# Un_Arduino_old.net
KiCad netlist of a schematic drawn in EAGLE
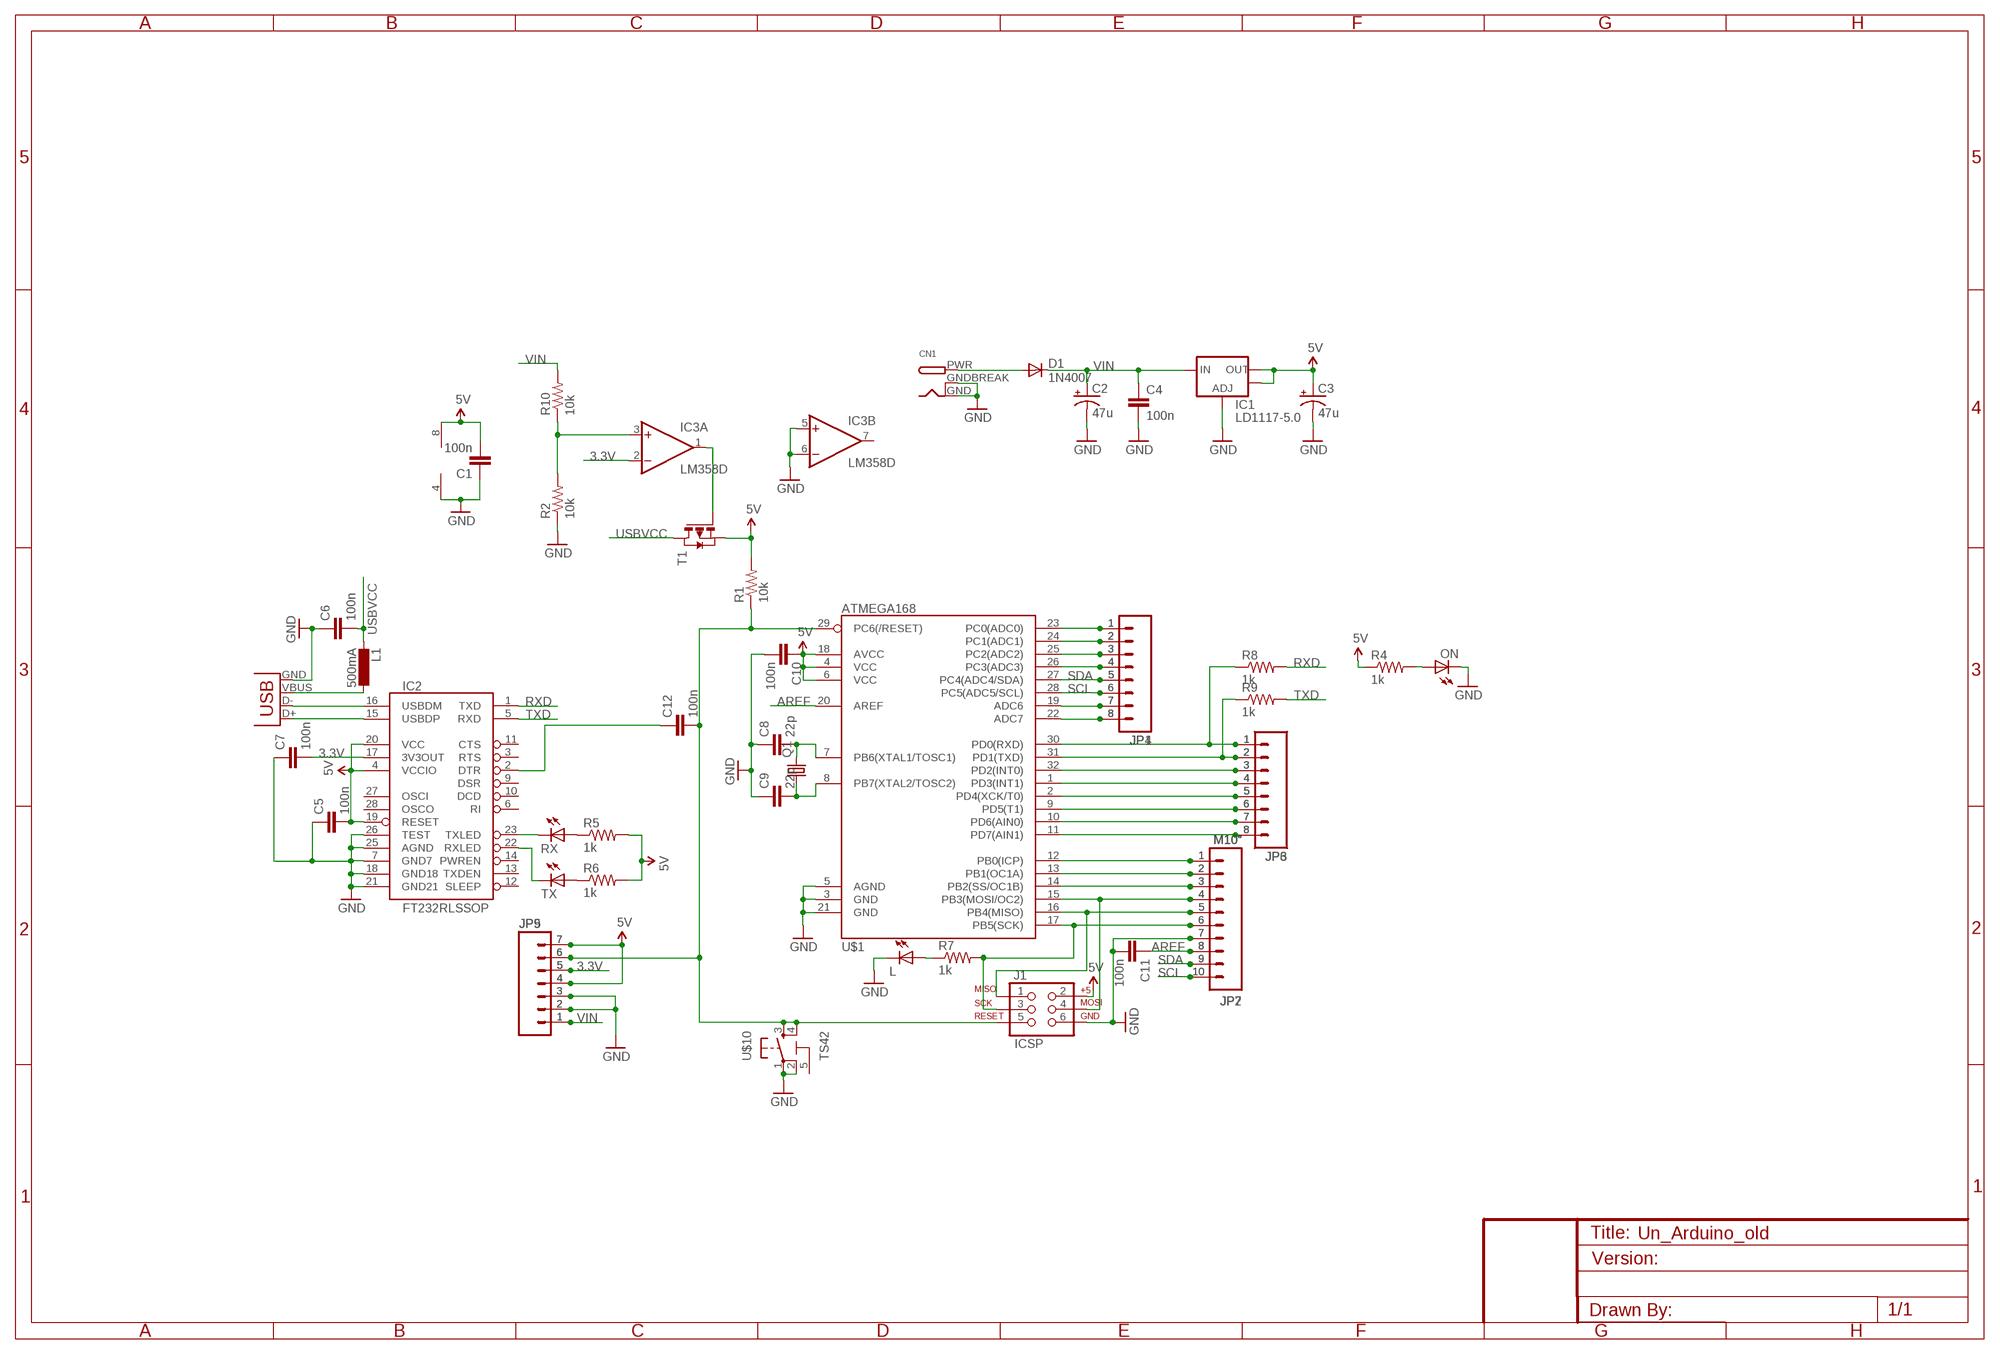
[diagram p0: schematic, sheet 1]

(export (version "E")
  (design (tool "Eeschema 10.0.6"))
  (components
    (comp (ref "C1")
      (value "100n")
      (footprint "eagle-import:0603-CAP")
      (libsource (lib "eagle-import") (part "CAP0603-CAP"))
    )
    (comp (ref "C2")
      (value "47u")
      (footprint "eagle-import:PANASONIC_D")
      (libsource (lib "eagle-import") (part "CAP_POLD"))
    )
    (comp (ref "C3")
      (value "47u")
      (footprint "eagle-import:PANASONIC_D")
      (libsource (lib "eagle-import") (part "CAP_POLD"))
    )
    (comp (ref "C4")
      (value "100n")
      (footprint "eagle-import:0603-CAP")
      (libsource (lib "eagle-import") (part "CAP0603-CAP"))
    )
    (comp (ref "C5")
      (value "100n")
      (footprint "eagle-import:0603-CAP")
      (libsource (lib "eagle-import") (part "CAP0603-CAP"))
    )
    (comp (ref "C6")
      (value "100n")
      (footprint "eagle-import:0603-CAP")
      (libsource (lib "eagle-import") (part "CAP0603-CAP"))
    )
    (comp (ref "C7")
      (value "100n")
      (footprint "eagle-import:0603-CAP")
      (libsource (lib "eagle-import") (part "CAP0603-CAP"))
    )
    (comp (ref "C8")
      (value "22p")
      (footprint "eagle-import:0805")
      (libsource (lib "eagle-import") (part "CAP0805"))
    )
    (comp (ref "C9")
      (value "22p")
      (footprint "eagle-import:0805")
      (libsource (lib "eagle-import") (part "CAP0805"))
    )
    (comp (ref "C10")
      (value "100n")
      (footprint "eagle-import:0603-CAP")
      (libsource (lib "eagle-import") (part "CAP0603-CAP"))
    )
    (comp (ref "C11")
      (value "100n")
      (footprint "eagle-import:0603-CAP")
      (libsource (lib "eagle-import") (part "CAP0603-CAP"))
    )
    (comp (ref "C12")
      (value "100n")
      (footprint "eagle-import:0603-CAP")
      (libsource (lib "eagle-import") (part "CAP0603-CAP"))
    )
    (comp (ref "CN1")
      (value "DCBARRELPTH")
      (footprint "eagle-import:DCJACK_2MM_PTH")
      (libsource (lib "eagle-import") (part "DCBARRELPTH"))
    )
    (comp (ref "D1")
      (value "1N4007")
      (footprint "eagle-import:SMB")
      (libsource (lib "eagle-import") (part "DIODE-SMB"))
    )
    (comp (ref "IC1")
      (value "LD1117-5.0")
      (footprint "eagle-import:SOT223")
      (libsource (lib "eagle-import") (part "V_REG_LM1117SOT223"))
    )
    (comp (ref "IC2")
      (value "FT232RLSSOP")
      (footprint "eagle-import:SSOP28DB")
      (libsource (lib "eagle-import") (part "FT232RLSSOP"))
    )
    (comp (ref "IC3")
      (value "LM358D")
      (footprint "eagle-import:SO08")
      (libsource (lib "eagle-import") (part "LM358D"))
    )
    (comp (ref "J1")
      (value "ICSP")
      (footprint "eagle-import:2X3")
      (libsource (lib "eagle-import") (part "AVR_SPI_PRG_6PTH"))
    )
    (comp (ref "JP1")
      (value "M081X08")
      (footprint "eagle-import:1X08")
      (libsource (lib "eagle-import") (part "M081X08"))
    )
    (comp (ref "JP2")
      (value "M10\"")
      (footprint "eagle-import:1X10")
      (libsource (lib "eagle-import") (part "M10{dblquote}"))
    )
    (comp (ref "JP3")
      (value "M08")
      (footprint "eagle-import:1X08")
      (libsource (lib "eagle-import") (part "M08"))
    )
    (comp (ref "JP4")
      (value "M081X08")
      (footprint "eagle-import:1X08")
      (libsource (lib "eagle-import") (part "M081X08"))
    )
    (comp (ref "JP5")
      (value "M07")
      (footprint "eagle-import:1X07")
      (libsource (lib "eagle-import") (part "M07"))
    )
    (comp (ref "JP6")
      (value "M08")
      (footprint "eagle-import:1X08")
      (libsource (lib "eagle-import") (part "M08"))
    )
    (comp (ref "JP7")
      (value "M10\"")
      (footprint "eagle-import:1X10")
      (libsource (lib "eagle-import") (part "M10{dblquote}"))
    )
    (comp (ref "JP9")
      (value "M07")
      (footprint "eagle-import:1X07")
      (libsource (lib "eagle-import") (part "M07"))
    )
    (comp (ref "L")
      (value "LED0805")
      (footprint "eagle-import:LED-0805")
      (libsource (lib "eagle-import") (part "LED0805"))
    )
    (comp (ref "L1")
      (value "500mA")
      (footprint "eagle-import:L1812")
      (libsource (lib "eagle-import") (part "L-EUL1812"))
    )
    (comp (ref "ON")
      (value "LED0805")
      (footprint "eagle-import:LED-0805")
      (libsource (lib "eagle-import") (part "LED0805"))
    )
    (comp (ref "Q1")
      (value "CRYSTALHC49US")
      (footprint "eagle-import:HC49US")
      (libsource (lib "eagle-import") (part "CRYSTALHC49US"))
    )
    (comp (ref "R1")
      (value "10k")
      (footprint "eagle-import:0805")
      (libsource (lib "eagle-import") (part "RESISTOR0805-RES"))
    )
    (comp (ref "R2")
      (value "10k")
      (footprint "eagle-import:0805")
      (libsource (lib "eagle-import") (part "RESISTOR0805-RES"))
    )
    (comp (ref "R4")
      (value "1k")
      (footprint "eagle-import:0805")
      (libsource (lib "eagle-import") (part "RESISTOR0805-RES"))
    )
    (comp (ref "R5")
      (value "1k")
      (footprint "eagle-import:0805")
      (libsource (lib "eagle-import") (part "RESISTOR0805-RES"))
    )
    (comp (ref "R6")
      (value "1k")
      (footprint "eagle-import:0805")
      (libsource (lib "eagle-import") (part "RESISTOR0805-RES"))
    )
    (comp (ref "R7")
      (value "1k")
      (footprint "eagle-import:0805")
      (libsource (lib "eagle-import") (part "RESISTOR0805-RES"))
    )
    (comp (ref "R8")
      (value "1k")
      (footprint "eagle-import:0805")
      (libsource (lib "eagle-import") (part "RESISTOR0805-RES"))
    )
    (comp (ref "R9")
      (value "1k")
      (footprint "eagle-import:0805")
      (libsource (lib "eagle-import") (part "RESISTOR0805-RES"))
    )
    (comp (ref "R10")
      (value "10k")
      (footprint "eagle-import:0805")
      (libsource (lib "eagle-import") (part "RESISTOR0805-RES"))
    )
    (comp (ref "RX")
      (value "LED0805")
      (footprint "eagle-import:LED-0805")
      (libsource (lib "eagle-import") (part "LED0805"))
    )
    (comp (ref "T1")
      (value "PMOSSOT23")
      (footprint "eagle-import:SOT-23")
      (libsource (lib "eagle-import") (part "PMOSSOT23"))
    )
    (comp (ref "TX")
      (value "LED0805")
      (footprint "eagle-import:LED-0805")
      (libsource (lib "eagle-import") (part "LED0805"))
    )
    (comp (ref "U$1")
      (value "ATMEGA168")
      (footprint "eagle-import:TQFP32-08")
      (libsource (lib "eagle-import") (part "ATMEGA168"))
    )
    (comp (ref "U$10")
      (value "TS42")
      (footprint "eagle-import:TS42")
      (libsource (lib "eagle-import") (part "TS42"))
    )
    (comp (ref "X1")
      (value "USBPTH")
      (footprint "eagle-import:USB-B-PTH")
      (libsource (lib "eagle-import") (part "USBPTH"))
    )
  )
  (nets
    (net (code "1") (name "/3.3V") (class "Default")
      (node (ref "C7") (pin "2") (pinfunction "2_2") (pintype "passive"))
      (node (ref "IC2") (pin "17") (pinfunction "3V3OUT_17") (pintype "output"))
      (node (ref "IC3") (pin "2") (pinfunction "-IN_2") (pintype "input"))
      (node (ref "JP5") (pin "5") (pinfunction "5_5") (pintype "passive"))
      (node (ref "JP9") (pin "5") (pinfunction "5_5") (pintype "passive"))
    )
    (net (code "2") (name "/AREF") (class "Default")
      (node (ref "C11") (pin "1") (pinfunction "1_1") (pintype "passive"))
      (node (ref "JP2") (pin "8") (pinfunction "8_8") (pintype "passive"))
      (node (ref "JP7") (pin "8") (pinfunction "8_8") (pintype "passive"))
      (node (ref "U$1") (pin "20") (pinfunction "AREF_20") (pintype "bidirectional"))
    )
    (net (code "3") (name "/RXD") (class "Default")
      (node (ref "IC2") (pin "1") (pinfunction "TXD_1") (pintype "output"))
      (node (ref "R8") (pin "2") (pinfunction "2_2") (pintype "passive"))
    )
    (net (code "4") (name "/SCL") (class "Default")
      (node (ref "JP1") (pin "6") (pinfunction "6_6") (pintype "passive"))
      (node (ref "JP2") (pin "10") (pinfunction "10_10") (pintype "passive"))
      (node (ref "JP4") (pin "6") (pinfunction "6_6") (pintype "passive"))
      (node (ref "JP7") (pin "10") (pinfunction "10_10") (pintype "passive"))
      (node (ref "U$1") (pin "28") (pinfunction "PC5(ADC5/SCL)_28") (pintype "bidirectional"))
    )
    (net (code "5") (name "/SDA") (class "Default")
      (node (ref "JP1") (pin "5") (pinfunction "5_5") (pintype "passive"))
      (node (ref "JP2") (pin "9") (pinfunction "9_9") (pintype "passive"))
      (node (ref "JP4") (pin "5") (pinfunction "5_5") (pintype "passive"))
      (node (ref "JP7") (pin "9") (pinfunction "9_9") (pintype "passive"))
      (node (ref "U$1") (pin "27") (pinfunction "PC4(ADC4/SDA)_27") (pintype "bidirectional"))
    )
    (net (code "6") (name "/TXD") (class "Default")
      (node (ref "IC2") (pin "5") (pinfunction "RXD_5") (pintype "input"))
      (node (ref "R9") (pin "2") (pinfunction "2_2") (pintype "passive"))
    )
    (net (code "7") (name "/USBVCC") (class "Default")
      (node (ref "C6") (pin "2") (pinfunction "2_2") (pintype "passive"))
      (node (ref "L1") (pin "2") (pinfunction "2_2") (pintype "passive"))
      (node (ref "T1") (pin "1") (pinfunction "D_1") (pintype "passive"))
    )
    (net (code "8") (name "/VIN") (class "Default")
      (node (ref "C2") (pin "+") (pinfunction "+_+") (pintype "passive"))
      (node (ref "C4") (pin "1") (pinfunction "1_1") (pintype "passive"))
      (node (ref "D1") (pin "C") (pinfunction "C_C") (pintype "passive"))
      (node (ref "IC1") (pin "3") (pinfunction "IN_3") (pintype "input"))
      (node (ref "JP5") (pin "1") (pinfunction "1_1") (pintype "passive"))
      (node (ref "JP9") (pin "1") (pinfunction "1_1") (pintype "passive"))
      (node (ref "R10") (pin "2") (pinfunction "2_2") (pintype "passive"))
    )
    (net (code "9") (name "5V") (class "Default")
      (node (ref "C1") (pin "2") (pinfunction "2_2") (pintype "passive"))
      (node (ref "C10") (pin "1") (pinfunction "1_1") (pintype "passive"))
      (node (ref "C3") (pin "+") (pinfunction "+_+") (pintype "passive"))
      (node (ref "C5") (pin "2") (pinfunction "2_2") (pintype "passive"))
      (node (ref "IC1") (pin "2") (pinfunction "OUT_2") (pintype "output"))
      (node (ref "IC1") (pin "4") (pinfunction "OUT_4") (pintype "output"))
      (node (ref "IC2") (pin "19") (pinfunction "RESET_19") (pintype "input"))
      (node (ref "IC2") (pin "20") (pinfunction "VCC_20") (pintype "power_in"))
      (node (ref "IC2") (pin "4") (pinfunction "VCCIO_4") (pintype "power_in"))
      (node (ref "IC3") (pin "8") (pinfunction "V+_8") (pintype "power_in"))
      (node (ref "J1") (pin "2") (pinfunction "2_2") (pintype "passive"))
      (node (ref "JP5") (pin "4") (pinfunction "4_4") (pintype "passive"))
      (node (ref "JP5") (pin "7") (pinfunction "7_7") (pintype "passive"))
      (node (ref "JP9") (pin "4") (pinfunction "4_4") (pintype "passive"))
      (node (ref "JP9") (pin "7") (pinfunction "7_7") (pintype "passive"))
      (node (ref "R1") (pin "2") (pinfunction "2_2") (pintype "passive"))
      (node (ref "R4") (pin "1") (pinfunction "1_1") (pintype "passive"))
      (node (ref "R5") (pin "2") (pinfunction "2_2") (pintype "passive"))
      (node (ref "R6") (pin "2") (pinfunction "2_2") (pintype "passive"))
      (node (ref "T1") (pin "2") (pinfunction "S_2") (pintype "passive"))
      (node (ref "U$1") (pin "18") (pinfunction "AVCC_18") (pintype "bidirectional"))
      (node (ref "U$1") (pin "4") (pinfunction "VCC_4") (pintype "bidirectional"))
      (node (ref "U$1") (pin "6") (pinfunction "VCC_6") (pintype "bidirectional"))
    )
    (net (code "10") (name "GND") (class "Default")
      (node (ref "C1") (pin "1") (pinfunction "1_1") (pintype "passive"))
      (node (ref "C10") (pin "2") (pinfunction "2_2") (pintype "passive"))
      (node (ref "C11") (pin "2") (pinfunction "2_2") (pintype "passive"))
      (node (ref "C2") (pin "-") (pinfunction "-_-") (pintype "passive"))
      (node (ref "C3") (pin "-") (pinfunction "-_-") (pintype "passive"))
      (node (ref "C4") (pin "2") (pinfunction "2_2") (pintype "passive"))
      (node (ref "C5") (pin "1") (pinfunction "1_1") (pintype "passive"))
      (node (ref "C6") (pin "1") (pinfunction "1_1") (pintype "passive"))
      (node (ref "C7") (pin "1") (pinfunction "1_1") (pintype "passive"))
      (node (ref "C8") (pin "1") (pinfunction "1_1") (pintype "passive"))
      (node (ref "C9") (pin "1") (pinfunction "1_1") (pintype "passive"))
      (node (ref "CN1") (pin "GND") (pinfunction "GND_GND") (pintype "power_in"))
      (node (ref "CN1") (pin "GNDBREAK") (pinfunction "GNDBREAK_GNDBREAK") (pintype "power_in"))
      (node (ref "IC1") (pin "1") (pinfunction "ADJ_1") (pintype "input"))
      (node (ref "IC2") (pin "18") (pinfunction "GND18_18") (pintype "power_in"))
      (node (ref "IC2") (pin "21") (pinfunction "GND21_21") (pintype "power_in"))
      (node (ref "IC2") (pin "25") (pinfunction "AGND_25") (pintype "power_in"))
      (node (ref "IC2") (pin "26") (pinfunction "TEST_26") (pintype "input"))
      (node (ref "IC2") (pin "7") (pinfunction "GND7_7") (pintype "power_in"))
      (node (ref "IC3") (pin "4") (pinfunction "V-_4") (pintype "power_in"))
      (node (ref "IC3") (pin "5") (pinfunction "+IN_5") (pintype "input"))
      (node (ref "IC3") (pin "6") (pinfunction "-IN_6") (pintype "input"))
      (node (ref "J1") (pin "6") (pinfunction "6_6") (pintype "passive"))
      (node (ref "JP2") (pin "7") (pinfunction "7_7") (pintype "passive"))
      (node (ref "JP5") (pin "2") (pinfunction "2_2") (pintype "passive"))
      (node (ref "JP5") (pin "3") (pinfunction "3_3") (pintype "passive"))
      (node (ref "JP7") (pin "7") (pinfunction "7_7") (pintype "passive"))
      (node (ref "JP9") (pin "2") (pinfunction "2_2") (pintype "passive"))
      (node (ref "JP9") (pin "3") (pinfunction "3_3") (pintype "passive"))
      (node (ref "L") (pin "2") (pinfunction "C_2") (pintype "passive"))
      (node (ref "ON") (pin "2") (pinfunction "C_2") (pintype "passive"))
      (node (ref "R2") (pin "1") (pinfunction "1_1") (pintype "passive"))
      (node (ref "U$1") (pin "21") (pinfunction "GND_21") (pintype "bidirectional"))
      (node (ref "U$1") (pin "3") (pinfunction "GND_3") (pintype "bidirectional"))
      (node (ref "U$1") (pin "5") (pinfunction "AGND_5") (pintype "bidirectional"))
      (node (ref "U$10") (pin "1") (pinfunction "1_1") (pintype "passive"))
      (node (ref "U$10") (pin "2") (pinfunction "2_2") (pintype "passive"))
      (node (ref "X1") (pin "GND") (pinfunction "GND_GND") (pintype "bidirectional"))
    )
    (net (code "11") (name "Net-(CN1-PadPWR)") (class "Default")
      (node (ref "CN1") (pin "PWR") (pinfunction "PWR_PWR") (pintype "power_in"))
      (node (ref "D1") (pin "A") (pinfunction "A_A") (pintype "passive"))
    )
    (net (code "12") (name "Net-(IC2-DTR)") (class "Default")
      (node (ref "C12") (pin "1") (pinfunction "1_1") (pintype "passive"))
      (node (ref "IC2") (pin "2") (pinfunction "DTR_2") (pintype "output"))
    )
    (net (code "13") (name "Net-(IC2-RXLED)") (class "Default")
      (node (ref "IC2") (pin "22") (pinfunction "RXLED_22") (pintype "input"))
      (node (ref "TX") (pin "2") (pinfunction "C_2") (pintype "passive"))
    )
    (net (code "14") (name "Net-(IC2-TXLED)") (class "Default")
      (node (ref "IC2") (pin "23") (pinfunction "TXLED_23") (pintype "input"))
      (node (ref "RX") (pin "2") (pinfunction "C_2") (pintype "passive"))
    )
    (net (code "15") (name "Net-(IC2-USBDM)") (class "Default")
      (node (ref "IC2") (pin "16") (pinfunction "USBDM_16") (pintype "bidirectional"))
      (node (ref "X1") (pin "D-") (pinfunction "D-_D-") (pintype "bidirectional"))
    )
    (net (code "16") (name "Net-(IC2-USBDP)") (class "Default")
      (node (ref "IC2") (pin "15") (pinfunction "USBDP_15") (pintype "bidirectional"))
      (node (ref "X1") (pin "D+") (pinfunction "D+_D+") (pintype "bidirectional"))
    )
    (net (code "17") (name "Net-(IC3A-+IN)") (class "Default")
      (node (ref "IC3") (pin "3") (pinfunction "+IN_3") (pintype "input"))
      (node (ref "R10") (pin "1") (pinfunction "1_1") (pintype "passive"))
      (node (ref "R2") (pin "2") (pinfunction "2_2") (pintype "passive"))
    )
    (net (code "18") (name "Net-(IC3A-OUT)") (class "Default")
      (node (ref "IC3") (pin "1") (pinfunction "OUT_1") (pintype "output"))
      (node (ref "T1") (pin "3") (pinfunction "G_3") (pintype "passive"))
    )
    (net (code "19") (name "Net-(L-A)") (class "Default")
      (node (ref "L") (pin "1") (pinfunction "A_1") (pintype "passive"))
      (node (ref "R7") (pin "1") (pinfunction "1_1") (pintype "passive"))
    )
    (net (code "20") (name "Net-(L1-Pad1)") (class "Default")
      (node (ref "L1") (pin "1") (pinfunction "1_1") (pintype "passive"))
      (node (ref "X1") (pin "VBUS") (pinfunction "VBUS_VBUS") (pintype "bidirectional"))
    )
    (net (code "21") (name "Net-(ON-A)") (class "Default")
      (node (ref "ON") (pin "1") (pinfunction "A_1") (pintype "passive"))
      (node (ref "R4") (pin "2") (pinfunction "2_2") (pintype "passive"))
    )
    (net (code "22") (name "Net-(RX-A)") (class "Default")
      (node (ref "R5") (pin "1") (pinfunction "1_1") (pintype "passive"))
      (node (ref "RX") (pin "1") (pinfunction "A_1") (pintype "passive"))
    )
    (net (code "23") (name "Net-(TX-A)") (class "Default")
      (node (ref "R6") (pin "1") (pinfunction "1_1") (pintype "passive"))
      (node (ref "TX") (pin "1") (pinfunction "A_1") (pintype "passive"))
    )
    (net (code "24") (name "Net-(U$1-ADC6)") (class "Default")
      (node (ref "JP1") (pin "7") (pinfunction "7_7") (pintype "passive"))
      (node (ref "JP4") (pin "7") (pinfunction "7_7") (pintype "passive"))
      (node (ref "U$1") (pin "19") (pinfunction "ADC6_19") (pintype "bidirectional"))
    )
    (net (code "25") (name "Net-(U$1-ADC7)") (class "Default")
      (node (ref "JP1") (pin "8") (pinfunction "8_8") (pintype "passive"))
      (node (ref "JP4") (pin "8") (pinfunction "8_8") (pintype "passive"))
      (node (ref "U$1") (pin "22") (pinfunction "ADC7_22") (pintype "bidirectional"))
    )
    (net (code "26") (name "Net-(U$1-PB0(ICP))") (class "Default")
      (node (ref "JP2") (pin "1") (pinfunction "1_1") (pintype "passive"))
      (node (ref "JP7") (pin "1") (pinfunction "1_1") (pintype "passive"))
      (node (ref "U$1") (pin "12") (pinfunction "PB0(ICP)_12") (pintype "bidirectional"))
    )
    (net (code "27") (name "Net-(U$1-PB1(OC1A))") (class "Default")
      (node (ref "JP2") (pin "2") (pinfunction "2_2") (pintype "passive"))
      (node (ref "JP7") (pin "2") (pinfunction "2_2") (pintype "passive"))
      (node (ref "U$1") (pin "13") (pinfunction "PB1(OC1A)_13") (pintype "bidirectional"))
    )
    (net (code "28") (name "Net-(U$1-PB2(SS{slash}OC1B))") (class "Default")
      (node (ref "JP2") (pin "3") (pinfunction "3_3") (pintype "passive"))
      (node (ref "JP7") (pin "3") (pinfunction "3_3") (pintype "passive"))
      (node (ref "U$1") (pin "14") (pinfunction "PB2(SS/OC1B)_14") (pintype "bidirectional"))
    )
    (net (code "29") (name "Net-(U$1-PB3(MOSI{slash}OC2))") (class "Default")
      (node (ref "J1") (pin "4") (pinfunction "4_4") (pintype "passive"))
      (node (ref "JP2") (pin "4") (pinfunction "4_4") (pintype "passive"))
      (node (ref "JP7") (pin "4") (pinfunction "4_4") (pintype "passive"))
      (node (ref "U$1") (pin "15") (pinfunction "PB3(MOSI/OC2)_15") (pintype "bidirectional"))
    )
    (net (code "30") (name "Net-(U$1-PB4(MISO))") (class "Default")
      (node (ref "J1") (pin "1") (pinfunction "1_1") (pintype "passive"))
      (node (ref "JP2") (pin "5") (pinfunction "5_5") (pintype "passive"))
      (node (ref "JP7") (pin "5") (pinfunction "5_5") (pintype "passive"))
      (node (ref "U$1") (pin "16") (pinfunction "PB4(MISO)_16") (pintype "bidirectional"))
    )
    (net (code "31") (name "Net-(U$1-PB5(SCK))") (class "Default")
      (node (ref "J1") (pin "3") (pinfunction "3_3") (pintype "passive"))
      (node (ref "JP2") (pin "6") (pinfunction "6_6") (pintype "passive"))
      (node (ref "JP7") (pin "6") (pinfunction "6_6") (pintype "passive"))
      (node (ref "R7") (pin "2") (pinfunction "2_2") (pintype "passive"))
      (node (ref "U$1") (pin "17") (pinfunction "PB5(SCK)_17") (pintype "bidirectional"))
    )
    (net (code "32") (name "Net-(U$1-PB6(XTAL1{slash}TOSC1))") (class "Default")
      (node (ref "C8") (pin "2") (pinfunction "2_2") (pintype "passive"))
      (node (ref "Q1") (pin "2") (pinfunction "2_2") (pintype "passive"))
      (node (ref "U$1") (pin "7") (pinfunction "PB6(XTAL1/TOSC1)_7") (pintype "bidirectional"))
    )
    (net (code "33") (name "Net-(U$1-PB7(XTAL2{slash}TOSC2))") (class "Default")
      (node (ref "C9") (pin "2") (pinfunction "2_2") (pintype "passive"))
      (node (ref "Q1") (pin "1") (pinfunction "1_1") (pintype "passive"))
      (node (ref "U$1") (pin "8") (pinfunction "PB7(XTAL2/TOSC2)_8") (pintype "bidirectional"))
    )
    (net (code "34") (name "Net-(U$1-PC0(ADC0))") (class "Default")
      (node (ref "JP1") (pin "1") (pinfunction "1_1") (pintype "passive"))
      (node (ref "JP4") (pin "1") (pinfunction "1_1") (pintype "passive"))
      (node (ref "U$1") (pin "23") (pinfunction "PC0(ADC0)_23") (pintype "bidirectional"))
    )
    (net (code "35") (name "Net-(U$1-PC1(ADC1))") (class "Default")
      (node (ref "JP1") (pin "2") (pinfunction "2_2") (pintype "passive"))
      (node (ref "JP4") (pin "2") (pinfunction "2_2") (pintype "passive"))
      (node (ref "U$1") (pin "24") (pinfunction "PC1(ADC1)_24") (pintype "bidirectional"))
    )
    (net (code "36") (name "Net-(U$1-PC2(ADC2))") (class "Default")
      (node (ref "JP1") (pin "3") (pinfunction "3_3") (pintype "passive"))
      (node (ref "JP4") (pin "3") (pinfunction "3_3") (pintype "passive"))
      (node (ref "U$1") (pin "25") (pinfunction "PC2(ADC2)_25") (pintype "bidirectional"))
    )
    (net (code "37") (name "Net-(U$1-PC3(ADC3))") (class "Default")
      (node (ref "JP1") (pin "4") (pinfunction "4_4") (pintype "passive"))
      (node (ref "JP4") (pin "4") (pinfunction "4_4") (pintype "passive"))
      (node (ref "U$1") (pin "26") (pinfunction "PC3(ADC3)_26") (pintype "bidirectional"))
    )
    (net (code "38") (name "Net-(U$1-PC6({slash}RESET))") (class "Default")
      (node (ref "C12") (pin "2") (pinfunction "2_2") (pintype "passive"))
      (node (ref "J1") (pin "5") (pinfunction "5_5") (pintype "passive"))
      (node (ref "JP5") (pin "6") (pinfunction "6_6") (pintype "passive"))
      (node (ref "JP9") (pin "6") (pinfunction "6_6") (pintype "passive"))
      (node (ref "R1") (pin "1") (pinfunction "1_1") (pintype "passive"))
      (node (ref "U$1") (pin "29") (pinfunction "PC6(/RESET)_29") (pintype "bidirectional"))
      (node (ref "U$10") (pin "3") (pinfunction "3_3") (pintype "passive"))
      (node (ref "U$10") (pin "4") (pinfunction "4_4") (pintype "passive"))
    )
    (net (code "39") (name "Net-(U$1-PD0(RXD))") (class "Default")
      (node (ref "JP3") (pin "1") (pinfunction "1_1") (pintype "passive"))
      (node (ref "JP6") (pin "1") (pinfunction "1_1") (pintype "passive"))
      (node (ref "R8") (pin "1") (pinfunction "1_1") (pintype "passive"))
      (node (ref "U$1") (pin "30") (pinfunction "PD0(RXD)_30") (pintype "bidirectional"))
    )
    (net (code "40") (name "Net-(U$1-PD1(TXD))") (class "Default")
      (node (ref "JP3") (pin "2") (pinfunction "2_2") (pintype "passive"))
      (node (ref "JP6") (pin "2") (pinfunction "2_2") (pintype "passive"))
      (node (ref "R9") (pin "1") (pinfunction "1_1") (pintype "passive"))
      (node (ref "U$1") (pin "31") (pinfunction "PD1(TXD)_31") (pintype "bidirectional"))
    )
    (net (code "41") (name "Net-(U$1-PD2(INT0))") (class "Default")
      (node (ref "JP3") (pin "3") (pinfunction "3_3") (pintype "passive"))
      (node (ref "JP6") (pin "3") (pinfunction "3_3") (pintype "passive"))
      (node (ref "U$1") (pin "32") (pinfunction "PD2(INT0)_32") (pintype "bidirectional"))
    )
    (net (code "42") (name "Net-(U$1-PD3(INT1))") (class "Default")
      (node (ref "JP3") (pin "4") (pinfunction "4_4") (pintype "passive"))
      (node (ref "JP6") (pin "4") (pinfunction "4_4") (pintype "passive"))
      (node (ref "U$1") (pin "1") (pinfunction "PD3(INT1)_1") (pintype "bidirectional"))
    )
    (net (code "43") (name "Net-(U$1-PD4(XCK{slash}T0))") (class "Default")
      (node (ref "JP3") (pin "5") (pinfunction "5_5") (pintype "passive"))
      (node (ref "JP6") (pin "5") (pinfunction "5_5") (pintype "passive"))
      (node (ref "U$1") (pin "2") (pinfunction "PD4(XCK/T0)_2") (pintype "bidirectional"))
    )
    (net (code "44") (name "Net-(U$1-PD5(T1))") (class "Default")
      (node (ref "JP3") (pin "6") (pinfunction "6_6") (pintype "passive"))
      (node (ref "JP6") (pin "6") (pinfunction "6_6") (pintype "passive"))
      (node (ref "U$1") (pin "9") (pinfunction "PD5(T1)_9") (pintype "bidirectional"))
    )
    (net (code "45") (name "Net-(U$1-PD6(AIN0))") (class "Default")
      (node (ref "JP3") (pin "7") (pinfunction "7_7") (pintype "passive"))
      (node (ref "JP6") (pin "7") (pinfunction "7_7") (pintype "passive"))
      (node (ref "U$1") (pin "10") (pinfunction "PD6(AIN0)_10") (pintype "bidirectional"))
    )
    (net (code "46") (name "Net-(U$1-PD7(AIN1))") (class "Default")
      (node (ref "JP3") (pin "8") (pinfunction "8_8") (pintype "passive"))
      (node (ref "JP6") (pin "8") (pinfunction "8_8") (pintype "passive"))
      (node (ref "U$1") (pin "11") (pinfunction "PD7(AIN1)_11") (pintype "bidirectional"))
    )
    (net (code "47") (name "unconnected-(IC2-CTS-Pad11)") (class "Default")
      (node (ref "IC2") (pin "11") (pinfunction "CTS_11") (pintype "input"))
    )
    (net (code "48") (name "unconnected-(IC2-DCD-Pad10)") (class "Default")
      (node (ref "IC2") (pin "10") (pinfunction "DCD_10") (pintype "input"))
    )
    (net (code "49") (name "unconnected-(IC2-DSR-Pad9)") (class "Default")
      (node (ref "IC2") (pin "9") (pinfunction "DSR_9") (pintype "input"))
    )
    (net (code "50") (name "unconnected-(IC2-OSCI-Pad27)") (class "Default")
      (node (ref "IC2") (pin "27") (pinfunction "OSCI_27") (pintype "input"))
    )
    (net (code "51") (name "unconnected-(IC2-OSCO-Pad28)") (class "Default")
      (node (ref "IC2") (pin "28") (pinfunction "OSCO_28") (pintype "output"))
    )
    (net (code "52") (name "unconnected-(IC2-PWREN-Pad14)") (class "Default")
      (node (ref "IC2") (pin "14") (pinfunction "PWREN_14") (pintype "input"))
    )
    (net (code "53") (name "unconnected-(IC2-RI-Pad6)") (class "Default")
      (node (ref "IC2") (pin "6") (pinfunction "RI_6") (pintype "input"))
    )
    (net (code "54") (name "unconnected-(IC2-RTS-Pad3)") (class "Default")
      (node (ref "IC2") (pin "3") (pinfunction "RTS_3") (pintype "output"))
    )
    (net (code "55") (name "unconnected-(IC2-SLEEP-Pad12)") (class "Default")
      (node (ref "IC2") (pin "12") (pinfunction "SLEEP_12") (pintype "input"))
    )
    (net (code "56") (name "unconnected-(IC2-TXDEN-Pad13)") (class "Default")
      (node (ref "IC2") (pin "13") (pinfunction "TXDEN_13") (pintype "input"))
    )
    (net (code "57") (name "unconnected-(IC3B-OUT-Pad7)") (class "Default")
      (node (ref "IC3") (pin "7") (pinfunction "OUT_7") (pintype "output"))
    )
    (net (code "58") (name "unconnected-(U$10-Pad5)") (class "Default")
      (node (ref "U$10") (pin "5") (pinfunction "5_5") (pintype "passive"))
    )
  )
)
